# UltrasonicSensor.net
KiCad netlist of a schematic drawn in EAGLE
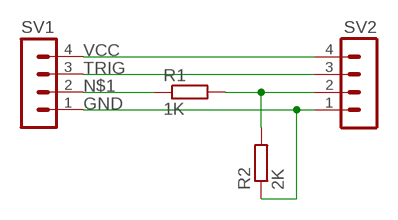
[diagram p0: schematic, sheet 1]

(export (version "E")
  (design (tool "Eeschema 10.0.6"))
  (components
    (comp (ref "R1")
      (value "1K")
      (footprint "eagle-import:0204_7")
      (libsource (lib "eagle-import") (part "R-EU_0204/7"))
    )
    (comp (ref "R2")
      (value "2K")
      (footprint "eagle-import:0204_7")
      (libsource (lib "eagle-import") (part "R-EU_0204/7"))
    )
    (comp (ref "SV1")
      (value "MA04-1")
      (footprint "eagle-import:MA04-1")
      (libsource (lib "eagle-import") (part "MA04-1"))
    )
    (comp (ref "SV2")
      (value "MA04-1")
      (footprint "eagle-import:MA04-1")
      (libsource (lib "eagle-import") (part "MA04-1"))
    )
  )
  (nets
    (net (code "1") (name "/GND") (class "Default")
      (node (ref "R2") (pin "1") (pinfunction "1_1") (pintype "passive"))
      (node (ref "SV1") (pin "1") (pinfunction "1_1") (pintype "passive"))
      (node (ref "SV2") (pin "1") (pinfunction "1_1") (pintype "passive"))
    )
    (net (code "2") (name "/N$1") (class "Default")
      (node (ref "R1") (pin "1") (pinfunction "1_1") (pintype "passive"))
      (node (ref "SV1") (pin "2") (pinfunction "2_2") (pintype "passive"))
    )
    (net (code "3") (name "/TRIG") (class "Default")
      (node (ref "SV1") (pin "3") (pinfunction "3_3") (pintype "passive"))
      (node (ref "SV2") (pin "3") (pinfunction "3_3") (pintype "passive"))
    )
    (net (code "4") (name "/VCC") (class "Default")
      (node (ref "SV1") (pin "4") (pinfunction "4_4") (pintype "passive"))
      (node (ref "SV2") (pin "4") (pinfunction "4_4") (pintype "passive"))
    )
    (net (code "5") (name "Net-(R1-Pad2)") (class "Default")
      (node (ref "R1") (pin "2") (pinfunction "2_2") (pintype "passive"))
      (node (ref "R2") (pin "2") (pinfunction "2_2") (pintype "passive"))
      (node (ref "SV2") (pin "2") (pinfunction "2_2") (pintype "passive"))
    )
  )
)
